# project_02.net
KiCad netlist of a schematic drawn in EAGLE
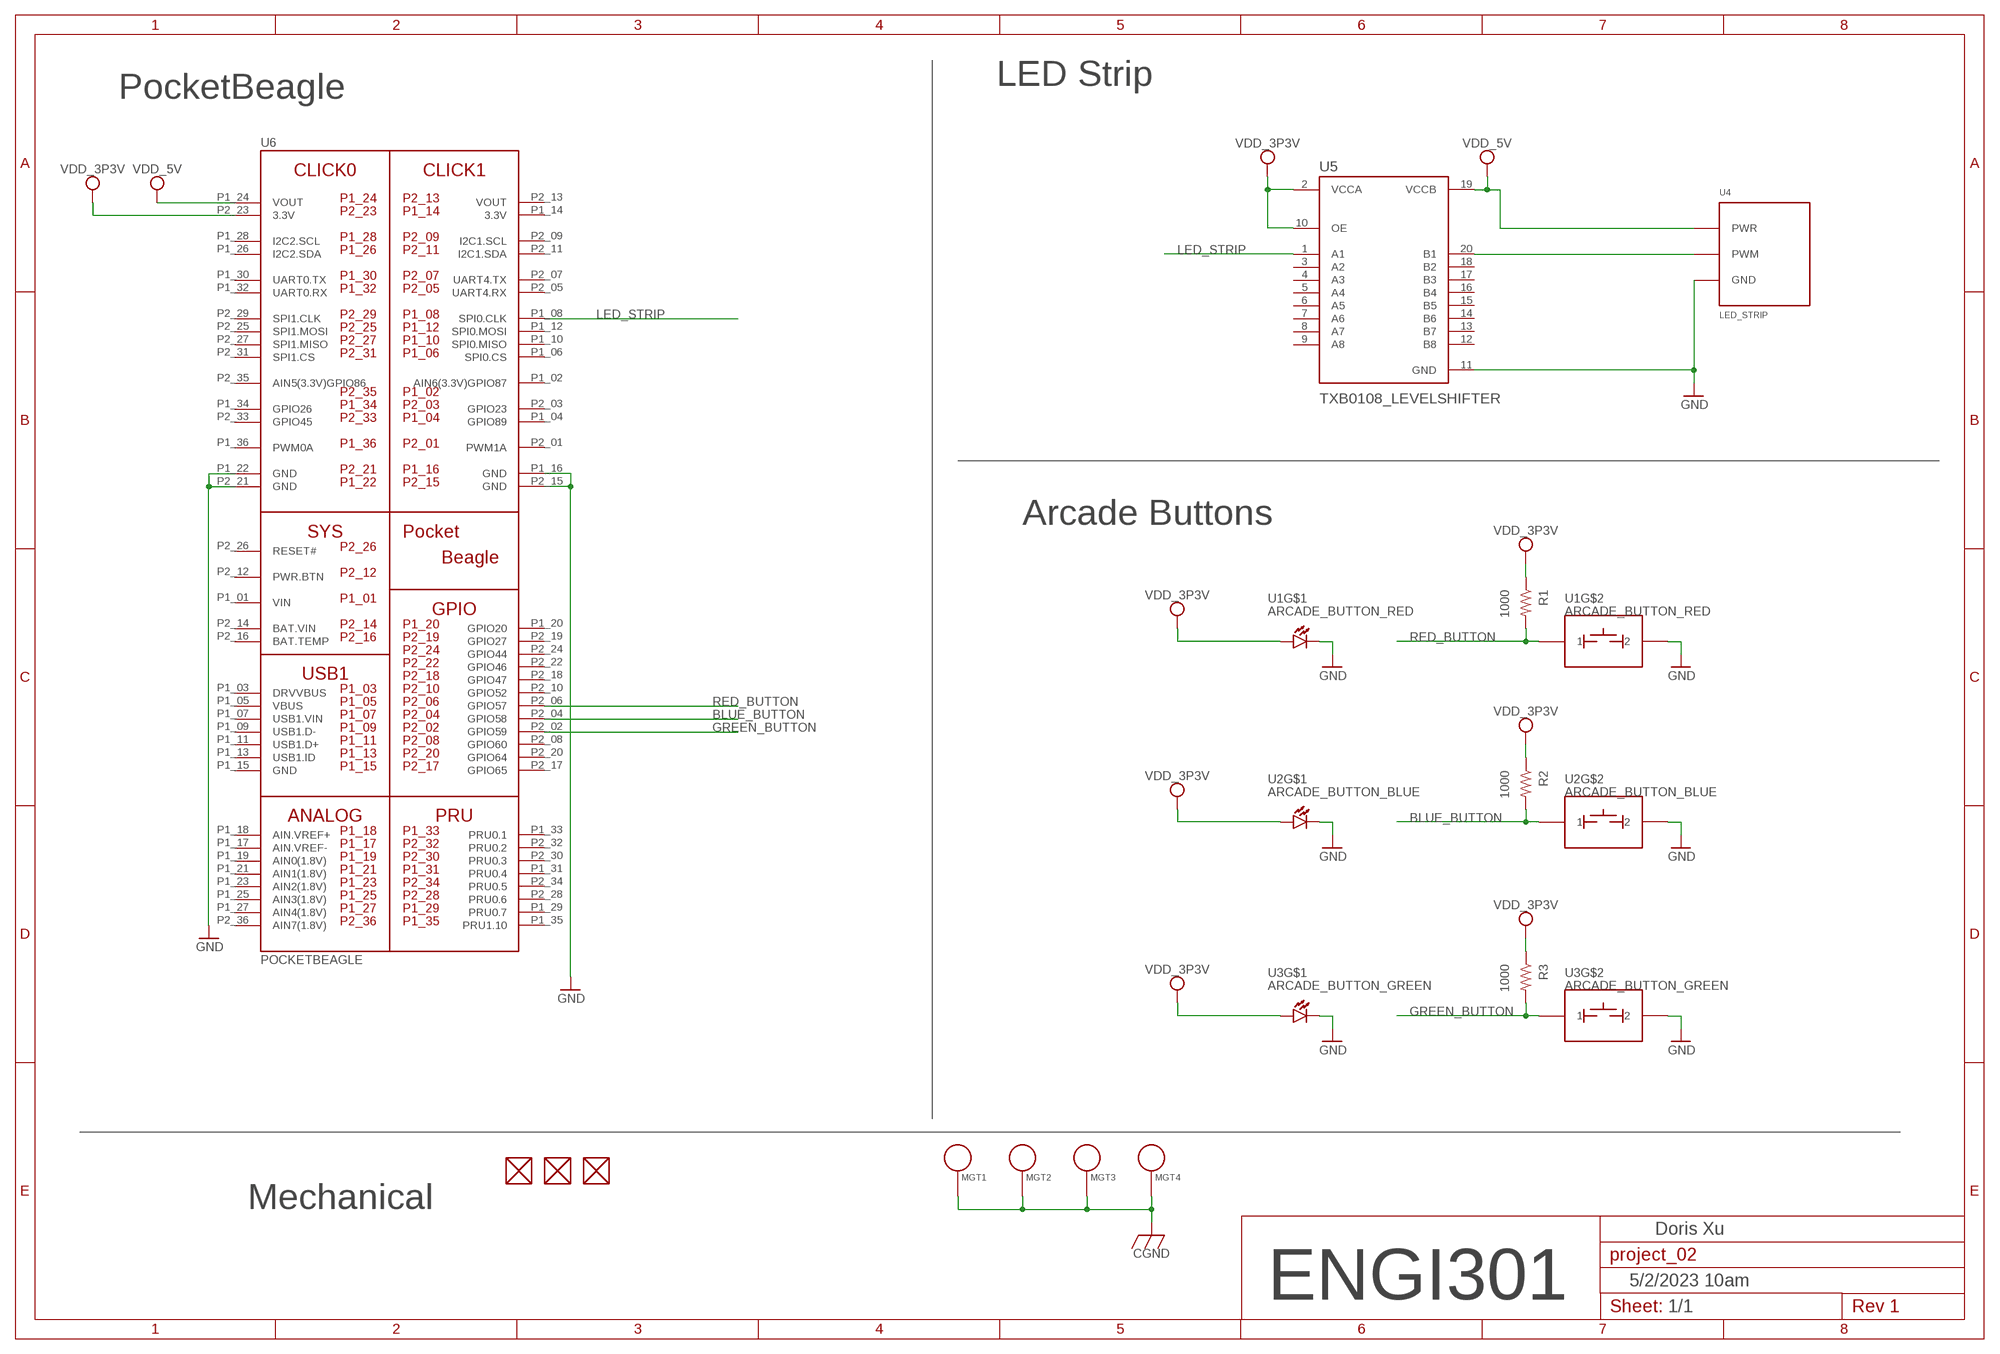
[diagram p0: schematic, sheet 1]

(export (version "E")
  (design (tool "Eeschema 10.0.6"))
  (components
    (comp (ref "FUD1")
      (value "FIDUCIAL")
      (footprint "eagle-import:FIDUCIAL_40MIL")
      (libsource (lib "eagle-import") (part "FIDUCIAL"))
    )
    (comp (ref "FUD2")
      (value "FIDUCIAL")
      (footprint "eagle-import:FIDUCIAL_40MIL")
      (libsource (lib "eagle-import") (part "FIDUCIAL"))
    )
    (comp (ref "FUD3")
      (value "FIDUCIAL")
      (footprint "eagle-import:FIDUCIAL_40MIL")
      (libsource (lib "eagle-import") (part "FIDUCIAL"))
    )
    (comp (ref "MGT1")
      (value "MOUNTING_HOLE")
      (footprint "eagle-import:MOUNTING_HOLE")
      (libsource (lib "eagle-import") (part "MOUNTING_HOLE"))
    )
    (comp (ref "MGT2")
      (value "MOUNTING_HOLE")
      (footprint "eagle-import:MOUNTING_HOLE")
      (libsource (lib "eagle-import") (part "MOUNTING_HOLE"))
    )
    (comp (ref "MGT3")
      (value "MOUNTING_HOLE")
      (footprint "eagle-import:MOUNTING_HOLE")
      (libsource (lib "eagle-import") (part "MOUNTING_HOLE"))
    )
    (comp (ref "MGT4")
      (value "MOUNTING_HOLE")
      (footprint "eagle-import:MOUNTING_HOLE")
      (libsource (lib "eagle-import") (part "MOUNTING_HOLE"))
    )
    (comp (ref "R1")
      (value "1000")
      (footprint "eagle-import:R1206")
      (libsource (lib "eagle-import") (part "R_R1206"))
    )
    (comp (ref "R2")
      (value "1000")
      (footprint "eagle-import:R1206")
      (libsource (lib "eagle-import") (part "R_R1206"))
    )
    (comp (ref "R3")
      (value "1000")
      (footprint "eagle-import:R1206")
      (libsource (lib "eagle-import") (part "R_R1206"))
    )
    (comp (ref "U1")
      (value "ARCADE_BUTTON_RED")
      (footprint "eagle-import:LED_BUTTON")
      (libsource (lib "eagle-import") (part "ARCADE_BUTTON"))
    )
    (comp (ref "U2")
      (value "ARCADE_BUTTON_BLUE")
      (footprint "eagle-import:LED_BUTTON")
      (libsource (lib "eagle-import") (part "ARCADE_BUTTON"))
    )
    (comp (ref "U3")
      (value "ARCADE_BUTTON_GREEN")
      (footprint "eagle-import:LED_BUTTON")
      (libsource (lib "eagle-import") (part "ARCADE_BUTTON"))
    )
    (comp (ref "U4")
      (value "LED_STRIP")
      (footprint "eagle-import:LED_STRIP")
      (libsource (lib "eagle-import") (part "LED_STRIP"))
    )
    (comp (ref "U5")
      (value "TXB0108_LEVELSHIFTER")
      (footprint "eagle-import:SOP65P640X120-20N")
      (fields (field (name "MF") "Texas Instruments") (field (name "MP") "TXB0108PWRG4"))
      (libsource (lib "eagle-import") (part "TXB0108_LEVELSHIFTER"))
    )
    (comp (ref "U6")
      (value "POCKETBEAGLE")
      (footprint "eagle-import:POCKETBEAGLE")
      (libsource (lib "eagle-import") (part "POCKETBEAGLE"))
    )
  )
  (nets
    (net (code "1") (name "/3.3V") (class "Default")
      (node (ref "U6") (pin "P1_14") (pinfunction "3.3V_P1_14") (pintype "power_in"))
    )
    (net (code "2") (name "/BAT.VIN") (class "Default")
      (node (ref "U6") (pin "P2_14") (pinfunction "BAT.VIN_P2_14") (pintype "power_in"))
    )
    (net (code "3") (name "/BLUE_BUTTON") (class "Default")
      (node (ref "R2") (pin "2") (pinfunction "2_2") (pintype "passive"))
      (node (ref "U2") (pin "BUTTON_1") (pinfunction "1_BUTTON_1") (pintype "bidirectional"))
      (node (ref "U6") (pin "P2_04") (pinfunction "GPIO58_P2_04") (pintype "bidirectional"))
    )
    (net (code "4") (name "/GREEN_BUTTON") (class "Default")
      (node (ref "R3") (pin "2") (pinfunction "2_2") (pintype "passive"))
      (node (ref "U3") (pin "BUTTON_1") (pinfunction "1_BUTTON_1") (pintype "bidirectional"))
      (node (ref "U6") (pin "P2_02") (pinfunction "GPIO59_P2_02") (pintype "bidirectional"))
    )
    (net (code "5") (name "/LED_STRIP") (class "Default")
      (node (ref "U5") (pin "1") (pinfunction "A1_1") (pintype "bidirectional"))
      (node (ref "U6") (pin "P1_08") (pinfunction "SPI0.CLK_P1_08") (pintype "bidirectional"))
    )
    (net (code "6") (name "/RED_BUTTON") (class "Default")
      (node (ref "R1") (pin "2") (pinfunction "2_2") (pintype "passive"))
      (node (ref "U1") (pin "BUTTON_1") (pinfunction "1_BUTTON_1") (pintype "bidirectional"))
      (node (ref "U6") (pin "P2_06") (pinfunction "GPIO57_P2_06") (pintype "bidirectional"))
    )
    (net (code "7") (name "/VIN") (class "Default")
      (node (ref "U6") (pin "P1_01") (pinfunction "VIN_P1_01") (pintype "power_in"))
    )
    (net (code "8") (name "/VOUT") (class "Default")
      (node (ref "U6") (pin "P2_13") (pinfunction "VOUT_P2_13") (pintype "power_in"))
    )
    (net (code "9") (name "CGND") (class "Default")
      (node (ref "MGT1") (pin "P$1") (pinfunction "P$1_P$1") (pintype "bidirectional"))
      (node (ref "MGT2") (pin "P$1") (pinfunction "P$1_P$1") (pintype "bidirectional"))
      (node (ref "MGT3") (pin "P$1") (pinfunction "P$1_P$1") (pintype "bidirectional"))
      (node (ref "MGT4") (pin "P$1") (pinfunction "P$1_P$1") (pintype "bidirectional"))
    )
    (net (code "10") (name "GND") (class "Default")
      (node (ref "U1") (pin "BUTTON_2") (pinfunction "2_BUTTON_2") (pintype "bidirectional"))
      (node (ref "U1") (pin "CATHODE") (pinfunction "CATHODE_CATHODE") (pintype "bidirectional"))
      (node (ref "U2") (pin "BUTTON_2") (pinfunction "2_BUTTON_2") (pintype "bidirectional"))
      (node (ref "U2") (pin "CATHODE") (pinfunction "CATHODE_CATHODE") (pintype "bidirectional"))
      (node (ref "U3") (pin "BUTTON_2") (pinfunction "2_BUTTON_2") (pintype "bidirectional"))
      (node (ref "U3") (pin "CATHODE") (pinfunction "CATHODE_CATHODE") (pintype "bidirectional"))
      (node (ref "U4") (pin "GND") (pinfunction "GND_GND") (pintype "bidirectional"))
      (node (ref "U5") (pin "11") (pinfunction "GND_11") (pintype "power_in"))
      (node (ref "U6") (pin "P1_16") (pinfunction "GND_P1_16") (pintype "power_in"))
      (node (ref "U6") (pin "P1_22") (pinfunction "GND_P1_22") (pintype "power_in"))
      (node (ref "U6") (pin "P2_15") (pinfunction "GND_P2_15") (pintype "power_in"))
      (node (ref "U6") (pin "P2_21") (pinfunction "GND_P2_21") (pintype "power_in"))
    )
    (net (code "11") (name "Net-(U4-PWM)") (class "Default")
      (node (ref "U4") (pin "SIG") (pinfunction "PWM_SIG") (pintype "bidirectional"))
      (node (ref "U5") (pin "20") (pinfunction "B1_20") (pintype "bidirectional"))
    )
    (net (code "12") (name "VDD_3P3V") (class "Default")
      (node (ref "R1") (pin "1") (pinfunction "1_1") (pintype "passive"))
      (node (ref "R2") (pin "1") (pinfunction "1_1") (pintype "passive"))
      (node (ref "R3") (pin "1") (pinfunction "1_1") (pintype "passive"))
      (node (ref "U1") (pin "ANODE") (pinfunction "ANODE_ANODE") (pintype "bidirectional"))
      (node (ref "U2") (pin "ANODE") (pinfunction "ANODE_ANODE") (pintype "bidirectional"))
      (node (ref "U3") (pin "ANODE") (pinfunction "ANODE_ANODE") (pintype "bidirectional"))
      (node (ref "U5") (pin "10") (pinfunction "OE_10") (pintype "input"))
      (node (ref "U5") (pin "2") (pinfunction "VCCA_2") (pintype "power_in"))
      (node (ref "U6") (pin "P2_23") (pinfunction "3.3V_P2_23") (pintype "power_in"))
    )
    (net (code "13") (name "VDD_5V") (class "Default")
      (node (ref "U4") (pin "PWR") (pinfunction "PWR_PWR") (pintype "bidirectional"))
      (node (ref "U5") (pin "19") (pinfunction "VCCB_19") (pintype "power_in"))
      (node (ref "U6") (pin "P1_24") (pinfunction "VOUT_P1_24") (pintype "power_in"))
    )
    (net (code "14") (name "unconnected-(FUD1-PadP$1)") (class "Default")
      (node (ref "FUD1") (pin "P$1") (pinfunction "P$1_P$1") (pintype "no_connect"))
    )
    (net (code "15") (name "unconnected-(FUD2-PadP$1)") (class "Default")
      (node (ref "FUD2") (pin "P$1") (pinfunction "P$1_P$1") (pintype "no_connect"))
    )
    (net (code "16") (name "unconnected-(FUD3-PadP$1)") (class "Default")
      (node (ref "FUD3") (pin "P$1") (pinfunction "P$1_P$1") (pintype "no_connect"))
    )
    (net (code "17") (name "unconnected-(U5-A2-Pad3)") (class "Default")
      (node (ref "U5") (pin "3") (pinfunction "A2_3") (pintype "bidirectional"))
    )
    (net (code "18") (name "unconnected-(U5-A3-Pad4)") (class "Default")
      (node (ref "U5") (pin "4") (pinfunction "A3_4") (pintype "bidirectional"))
    )
    (net (code "19") (name "unconnected-(U5-A4-Pad5)") (class "Default")
      (node (ref "U5") (pin "5") (pinfunction "A4_5") (pintype "bidirectional"))
    )
    (net (code "20") (name "unconnected-(U5-A5-Pad6)") (class "Default")
      (node (ref "U5") (pin "6") (pinfunction "A5_6") (pintype "bidirectional"))
    )
    (net (code "21") (name "unconnected-(U5-A6-Pad7)") (class "Default")
      (node (ref "U5") (pin "7") (pinfunction "A6_7") (pintype "bidirectional"))
    )
    (net (code "22") (name "unconnected-(U5-A7-Pad8)") (class "Default")
      (node (ref "U5") (pin "8") (pinfunction "A7_8") (pintype "bidirectional"))
    )
    (net (code "23") (name "unconnected-(U5-A8-Pad9)") (class "Default")
      (node (ref "U5") (pin "9") (pinfunction "A8_9") (pintype "bidirectional"))
    )
    (net (code "24") (name "unconnected-(U5-B2-Pad18)") (class "Default")
      (node (ref "U5") (pin "18") (pinfunction "B2_18") (pintype "bidirectional"))
    )
    (net (code "25") (name "unconnected-(U5-B3-Pad17)") (class "Default")
      (node (ref "U5") (pin "17") (pinfunction "B3_17") (pintype "bidirectional"))
    )
    (net (code "26") (name "unconnected-(U5-B4-Pad16)") (class "Default")
      (node (ref "U5") (pin "16") (pinfunction "B4_16") (pintype "bidirectional"))
    )
    (net (code "27") (name "unconnected-(U5-B5-Pad15)") (class "Default")
      (node (ref "U5") (pin "15") (pinfunction "B5_15") (pintype "bidirectional"))
    )
    (net (code "28") (name "unconnected-(U5-B6-Pad14)") (class "Default")
      (node (ref "U5") (pin "14") (pinfunction "B6_14") (pintype "bidirectional"))
    )
    (net (code "29") (name "unconnected-(U5-B7-Pad13)") (class "Default")
      (node (ref "U5") (pin "13") (pinfunction "B7_13") (pintype "bidirectional"))
    )
    (net (code "30") (name "unconnected-(U5-B8-Pad12)") (class "Default")
      (node (ref "U5") (pin "12") (pinfunction "B8_12") (pintype "bidirectional"))
    )
    (net (code "31") (name "unconnected-(U6-AIN.VREF+-PadP1_18)") (class "Default")
      (node (ref "U6") (pin "P1_18") (pinfunction "AIN.VREF+_P1_18") (pintype "input"))
    )
    (net (code "32") (name "unconnected-(U6-AIN.VREF--PadP1_17)") (class "Default")
      (node (ref "U6") (pin "P1_17") (pinfunction "AIN.VREF-_P1_17") (pintype "input"))
    )
    (net (code "33") (name "unconnected-(U6-AIN0(1.8V)-PadP1_19)") (class "Default")
      (node (ref "U6") (pin "P1_19") (pinfunction "AIN0(1.8V)_P1_19") (pintype "input"))
    )
    (net (code "34") (name "unconnected-(U6-AIN1(1.8V)-PadP1_21)") (class "Default")
      (node (ref "U6") (pin "P1_21") (pinfunction "AIN1(1.8V)_P1_21") (pintype "input"))
    )
    (net (code "35") (name "unconnected-(U6-AIN2(1.8V)-PadP1_23)") (class "Default")
      (node (ref "U6") (pin "P1_23") (pinfunction "AIN2(1.8V)_P1_23") (pintype "input"))
    )
    (net (code "36") (name "unconnected-(U6-AIN3(1.8V)-PadP1_25)") (class "Default")
      (node (ref "U6") (pin "P1_25") (pinfunction "AIN3(1.8V)_P1_25") (pintype "input"))
    )
    (net (code "37") (name "unconnected-(U6-AIN4(1.8V)-PadP1_27)") (class "Default")
      (node (ref "U6") (pin "P1_27") (pinfunction "AIN4(1.8V)_P1_27") (pintype "input"))
    )
    (net (code "38") (name "unconnected-(U6-AIN5(3.3V)GPIO86-PadP2_35)") (class "Default")
      (node (ref "U6") (pin "P2_35") (pinfunction "AIN5(3.3V)GPIO86_P2_35") (pintype "bidirectional"))
    )
    (net (code "39") (name "unconnected-(U6-AIN6(3.3V)GPIO87-PadP1_02)") (class "Default")
      (node (ref "U6") (pin "P1_02") (pinfunction "AIN6(3.3V)GPIO87_P1_02") (pintype "bidirectional"))
    )
    (net (code "40") (name "unconnected-(U6-AIN7(1.8V)-PadP2_36)") (class "Default")
      (node (ref "U6") (pin "P2_36") (pinfunction "AIN7(1.8V)_P2_36") (pintype "input"))
    )
    (net (code "41") (name "unconnected-(U6-BAT.TEMP-PadP2_16)") (class "Default")
      (node (ref "U6") (pin "P2_16") (pinfunction "BAT.TEMP_P2_16") (pintype "input"))
    )
    (net (code "42") (name "unconnected-(U6-DRVVBUS-PadP1_03)") (class "Default")
      (node (ref "U6") (pin "P1_03") (pinfunction "DRVVBUS_P1_03") (pintype "bidirectional"))
    )
    (net (code "43") (name "unconnected-(U6-GND-PadP1_15)") (class "Default")
      (node (ref "U6") (pin "P1_15") (pinfunction "GND_P1_15") (pintype "bidirectional"))
    )
    (net (code "44") (name "unconnected-(U6-GPIO20-PadP1_20)") (class "Default")
      (node (ref "U6") (pin "P1_20") (pinfunction "GPIO20_P1_20") (pintype "bidirectional"))
    )
    (net (code "45") (name "unconnected-(U6-GPIO23-PadP2_03)") (class "Default")
      (node (ref "U6") (pin "P2_03") (pinfunction "GPIO23_P2_03") (pintype "bidirectional"))
    )
    (net (code "46") (name "unconnected-(U6-GPIO26-PadP1_34)") (class "Default")
      (node (ref "U6") (pin "P1_34") (pinfunction "GPIO26_P1_34") (pintype "bidirectional"))
    )
    (net (code "47") (name "unconnected-(U6-GPIO27-PadP2_19)") (class "Default")
      (node (ref "U6") (pin "P2_19") (pinfunction "GPIO27_P2_19") (pintype "bidirectional"))
    )
    (net (code "48") (name "unconnected-(U6-GPIO44-PadP2_24)") (class "Default")
      (node (ref "U6") (pin "P2_24") (pinfunction "GPIO44_P2_24") (pintype "bidirectional"))
    )
    (net (code "49") (name "unconnected-(U6-GPIO45-PadP2_33)") (class "Default")
      (node (ref "U6") (pin "P2_33") (pinfunction "GPIO45_P2_33") (pintype "bidirectional"))
    )
    (net (code "50") (name "unconnected-(U6-GPIO46-PadP2_22)") (class "Default")
      (node (ref "U6") (pin "P2_22") (pinfunction "GPIO46_P2_22") (pintype "bidirectional"))
    )
    (net (code "51") (name "unconnected-(U6-GPIO47-PadP2_18)") (class "Default")
      (node (ref "U6") (pin "P2_18") (pinfunction "GPIO47_P2_18") (pintype "bidirectional"))
    )
    (net (code "52") (name "unconnected-(U6-GPIO52-PadP2_10)") (class "Default")
      (node (ref "U6") (pin "P2_10") (pinfunction "GPIO52_P2_10") (pintype "bidirectional"))
    )
    (net (code "53") (name "unconnected-(U6-GPIO60-PadP2_08)") (class "Default")
      (node (ref "U6") (pin "P2_08") (pinfunction "GPIO60_P2_08") (pintype "bidirectional"))
    )
    (net (code "54") (name "unconnected-(U6-GPIO64-PadP2_20)") (class "Default")
      (node (ref "U6") (pin "P2_20") (pinfunction "GPIO64_P2_20") (pintype "bidirectional"))
    )
    (net (code "55") (name "unconnected-(U6-GPIO65-PadP2_17)") (class "Default")
      (node (ref "U6") (pin "P2_17") (pinfunction "GPIO65_P2_17") (pintype "bidirectional"))
    )
    (net (code "56") (name "unconnected-(U6-GPIO89-PadP1_04)") (class "Default")
      (node (ref "U6") (pin "P1_04") (pinfunction "GPIO89_P1_04") (pintype "bidirectional"))
    )
    (net (code "57") (name "unconnected-(U6-I2C1.SCL-PadP2_09)") (class "Default")
      (node (ref "U6") (pin "P2_09") (pinfunction "I2C1.SCL_P2_09") (pintype "bidirectional"))
    )
    (net (code "58") (name "unconnected-(U6-I2C1.SDA-PadP2_11)") (class "Default")
      (node (ref "U6") (pin "P2_11") (pinfunction "I2C1.SDA_P2_11") (pintype "bidirectional"))
    )
    (net (code "59") (name "unconnected-(U6-I2C2.SCL-PadP1_28)") (class "Default")
      (node (ref "U6") (pin "P1_28") (pinfunction "I2C2.SCL_P1_28") (pintype "bidirectional"))
    )
    (net (code "60") (name "unconnected-(U6-I2C2.SDA-PadP1_26)") (class "Default")
      (node (ref "U6") (pin "P1_26") (pinfunction "I2C2.SDA_P1_26") (pintype "bidirectional"))
    )
    (net (code "61") (name "unconnected-(U6-PRU0.1-PadP1_33)") (class "Default")
      (node (ref "U6") (pin "P1_33") (pinfunction "PRU0.1_P1_33") (pintype "bidirectional"))
    )
    (net (code "62") (name "unconnected-(U6-PRU0.2-PadP2_32)") (class "Default")
      (node (ref "U6") (pin "P2_32") (pinfunction "PRU0.2_P2_32") (pintype "bidirectional"))
    )
    (net (code "63") (name "unconnected-(U6-PRU0.3-PadP2_30)") (class "Default")
      (node (ref "U6") (pin "P2_30") (pinfunction "PRU0.3_P2_30") (pintype "bidirectional"))
    )
    (net (code "64") (name "unconnected-(U6-PRU0.4-PadP1_31)") (class "Default")
      (node (ref "U6") (pin "P1_31") (pinfunction "PRU0.4_P1_31") (pintype "bidirectional"))
    )
    (net (code "65") (name "unconnected-(U6-PRU0.5-PadP2_34)") (class "Default")
      (node (ref "U6") (pin "P2_34") (pinfunction "PRU0.5_P2_34") (pintype "bidirectional"))
    )
    (net (code "66") (name "unconnected-(U6-PRU0.6-PadP2_28)") (class "Default")
      (node (ref "U6") (pin "P2_28") (pinfunction "PRU0.6_P2_28") (pintype "bidirectional"))
    )
    (net (code "67") (name "unconnected-(U6-PRU0.7-PadP1_29)") (class "Default")
      (node (ref "U6") (pin "P1_29") (pinfunction "PRU0.7_P1_29") (pintype "bidirectional"))
    )
    (net (code "68") (name "unconnected-(U6-PRU1.10-PadP1_35)") (class "Default")
      (node (ref "U6") (pin "P1_35") (pinfunction "PRU1.10_P1_35") (pintype "bidirectional"))
    )
    (net (code "69") (name "unconnected-(U6-PWM0A-PadP1_36)") (class "Default")
      (node (ref "U6") (pin "P1_36") (pinfunction "PWM0A_P1_36") (pintype "bidirectional"))
    )
    (net (code "70") (name "unconnected-(U6-PWM1A-PadP2_01)") (class "Default")
      (node (ref "U6") (pin "P2_01") (pinfunction "PWM1A_P2_01") (pintype "bidirectional"))
    )
    (net (code "71") (name "unconnected-(U6-PWR.BTN-PadP2_12)") (class "Default")
      (node (ref "U6") (pin "P2_12") (pinfunction "PWR.BTN_P2_12") (pintype "input"))
    )
    (net (code "72") (name "unconnected-(U6-RESET#-PadP2_26)") (class "Default")
      (node (ref "U6") (pin "P2_26") (pinfunction "RESET#_P2_26") (pintype "input"))
    )
    (net (code "73") (name "unconnected-(U6-SPI0.CS-PadP1_06)") (class "Default")
      (node (ref "U6") (pin "P1_06") (pinfunction "SPI0.CS_P1_06") (pintype "bidirectional"))
    )
    (net (code "74") (name "unconnected-(U6-SPI0.MISO-PadP1_10)") (class "Default")
      (node (ref "U6") (pin "P1_10") (pinfunction "SPI0.MISO_P1_10") (pintype "bidirectional"))
    )
    (net (code "75") (name "unconnected-(U6-SPI0.MOSI-PadP1_12)") (class "Default")
      (node (ref "U6") (pin "P1_12") (pinfunction "SPI0.MOSI_P1_12") (pintype "bidirectional"))
    )
    (net (code "76") (name "unconnected-(U6-SPI1.CLK-PadP2_29)") (class "Default")
      (node (ref "U6") (pin "P2_29") (pinfunction "SPI1.CLK_P2_29") (pintype "bidirectional"))
    )
    (net (code "77") (name "unconnected-(U6-SPI1.CS-PadP2_31)") (class "Default")
      (node (ref "U6") (pin "P2_31") (pinfunction "SPI1.CS_P2_31") (pintype "bidirectional"))
    )
    (net (code "78") (name "unconnected-(U6-SPI1.MISO-PadP2_27)") (class "Default")
      (node (ref "U6") (pin "P2_27") (pinfunction "SPI1.MISO_P2_27") (pintype "bidirectional"))
    )
    (net (code "79") (name "unconnected-(U6-SPI1.MOSI-PadP2_25)") (class "Default")
      (node (ref "U6") (pin "P2_25") (pinfunction "SPI1.MOSI_P2_25") (pintype "bidirectional"))
    )
    (net (code "80") (name "unconnected-(U6-UART0.RX-PadP1_32)") (class "Default")
      (node (ref "U6") (pin "P1_32") (pinfunction "UART0.RX_P1_32") (pintype "bidirectional"))
    )
    (net (code "81") (name "unconnected-(U6-UART0.TX-PadP1_30)") (class "Default")
      (node (ref "U6") (pin "P1_30") (pinfunction "UART0.TX_P1_30") (pintype "bidirectional"))
    )
    (net (code "82") (name "unconnected-(U6-UART4.RX-PadP2_05)") (class "Default")
      (node (ref "U6") (pin "P2_05") (pinfunction "UART4.RX_P2_05") (pintype "bidirectional"))
    )
    (net (code "83") (name "unconnected-(U6-UART4.TX-PadP2_07)") (class "Default")
      (node (ref "U6") (pin "P2_07") (pinfunction "UART4.TX_P2_07") (pintype "bidirectional"))
    )
    (net (code "84") (name "unconnected-(U6-USB1.D+-PadP1_11)") (class "Default")
      (node (ref "U6") (pin "P1_11") (pinfunction "USB1.D+_P1_11") (pintype "bidirectional"))
    )
    (net (code "85") (name "unconnected-(U6-USB1.D--PadP1_09)") (class "Default")
      (node (ref "U6") (pin "P1_09") (pinfunction "USB1.D-_P1_09") (pintype "bidirectional"))
    )
    (net (code "86") (name "unconnected-(U6-USB1.ID-PadP1_13)") (class "Default")
      (node (ref "U6") (pin "P1_13") (pinfunction "USB1.ID_P1_13") (pintype "bidirectional"))
    )
    (net (code "87") (name "unconnected-(U6-USB1.VIN-PadP1_07)") (class "Default")
      (node (ref "U6") (pin "P1_07") (pinfunction "USB1.VIN_P1_07") (pintype "bidirectional"))
    )
    (net (code "88") (name "unconnected-(U6-VBUS-PadP1_05)") (class "Default")
      (node (ref "U6") (pin "P1_05") (pinfunction "VBUS_P1_05") (pintype "bidirectional"))
    )
  )
)
